# S_Phase_Sense_Signal_Isolation.net
KiCad netlist of a schematic drawn in Altium Designer
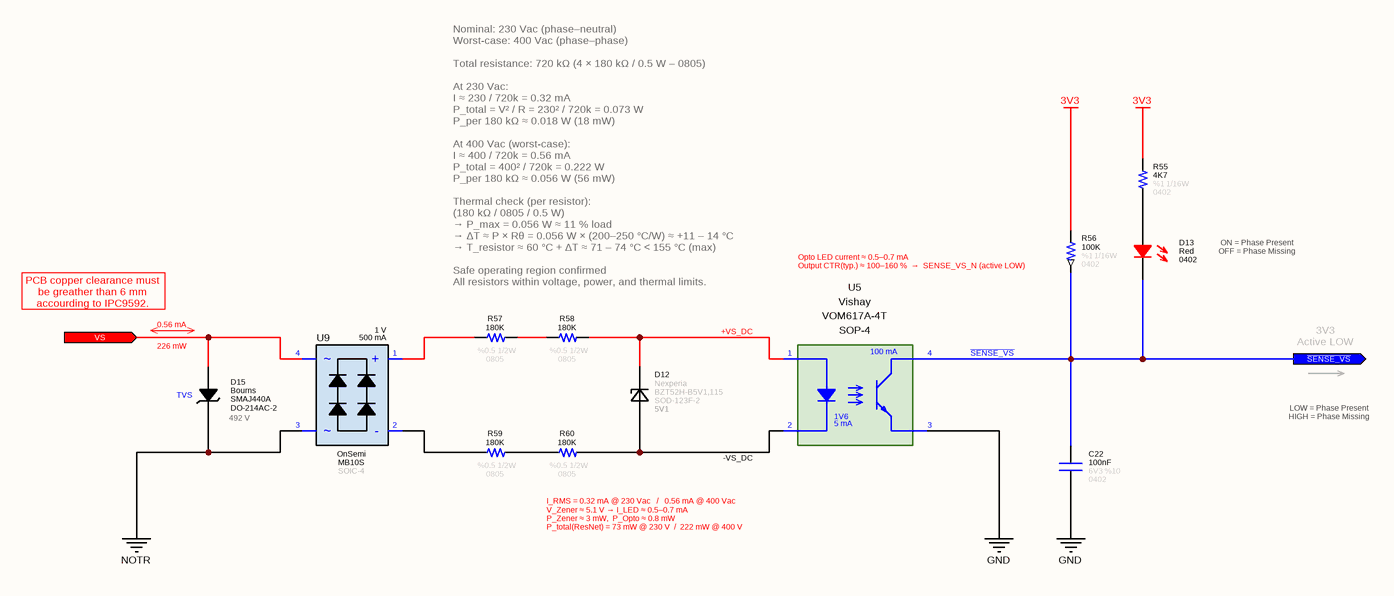
[diagram p0: S Phase Sense Signal Isolation.SchDoc]

(export (version "E")
  (design (tool "Eeschema 10.0.6"))
  (components
    (comp (ref "C22")
      (value "100nF")
      (footprint "CAPACITOR_0402")
      (description "Capacitor (MLCC) - 100nF / 6V3 / 0402")
      (fields
        (field (name "MANUFACTURER PART NUMBER") "04026D104KAT4A")
        (field (name "TOLERANCE") "%10")
        (field (name "VOLTAGE") "6V3")
        (field (name "CASE") "0402")
        (field (name "Comment") "Capacitor - 100nF [0402] (MLCC)")
      )
      (libsource (lib "Akkoyun") (part "Capacitor - 100nF [0402-6V3]"))
    )
    (comp (ref "D12")
      (value "BZT52H-B5V1,115")
      (footprint "SOD-123F-2")
      (description "Zener Diodes BZT52H-B5V1/SOD123F/SOD2")
      (fields
        (field (name "ZENER VOLTAGE") "5V1")
        (field (name "MANUFACTURER NAME") "Nexperia")
        (field (name "MANUFACTURER PART NUMBER") "BZT52H-B5V1,115")
        (field (name "CASE") "SOD-123F-2")
      )
      (libsource (lib "Akkoyun") (part "Diode - BZT52H-B5V1,115"))
    )
    (comp (ref "D13")
      (value "SMD LED (Red)")
      (footprint "LED_0402")
      (description "Standard LEDs - SMD MINI-MOLD ULTRA COMPACT RED")
      (fields
        (field (name "MANUFACTURER PART NUMBER") "SML-P12VTT86R")
        (field (name "CASE") "0402")
        (field (name "COLOR") "Red")
      )
      (libsource (lib "Akkoyun") (part "Diode - LED (0402-Red)"))
    )
    (comp (ref "D15")
      (value "SMAJ440A")
      (footprint "DO-220AA-2")
      (description "ESD Protection Diodes / TVS Diodes 440volts 1uA .6 Amps Uni-Dir")
      (fields
        (field (name "BREAKDOWN VOLTAGE") "492 V")
        (field (name "MANUFACTURER NAME") "Bourns")
        (field (name "MANUFACTURER PART NUMBER") "SMAJ440A")
        (field (name "CASE") "DO-214AC-2")
      )
      (libsource (lib "Akkoyun") (part "Diode - SMAJ440A (TVS)"))
    )
    (comp (ref "R55")
      (value "4K7")
      (footprint "RESISTOR_0402")
      (description "Thick Film Resistors - SMD 1/16 W 4.7 KOhm 1%")
      (fields
        (field (name "MANUFACTURER PART NUMBER") "CRCW04024K70FKED")
        (field (name "TOLERANCE") "%1")
        (field (name "CASE") "0402")
        (field (name "POWER") "1/16W")
        (field (name "Comment") "4K7 - 0402 - %1 - 1/16W")
      )
      (libsource (lib "Akkoyun") (part "Resistor - 4K7 [0402]"))
    )
    (comp (ref "R56")
      (value "100K")
      (footprint "RESISTOR_0402")
      (description "Thick Film Resistors - SMD 1/16 W 100 KOhm 1%")
      (fields
        (field (name "MANUFACTURER PART NUMBER") "CRCW0402100KFKED")
        (field (name "TOLERANCE") "%1")
        (field (name "CASE") "0402")
        (field (name "POWER") "1/16W")
        (field (name "Comment") "100K - 0402 - %1 - 1/16W")
      )
      (libsource (lib "Akkoyun") (part "Resistor - 100K [0402]"))
    )
    (comp (ref "R57")
      (value "180K")
      (footprint "RESISTOR_0805")
      (description "Thick Film Resistors - SMD 0805 180Kohms 0.5W 0.5% AEC-Q200")
      (fields
        (field (name "MANUFACTURER PART NUMBER") "ERJ-P06D1803V")
        (field (name "TOLERANCE") "%0.5")
        (field (name "CASE") "0805")
        (field (name "POWER") "1/2W")
        (field (name "Comment") "180K - 0805 - %0.5 - 1/2W")
      )
      (libsource (lib "Akkoyun") (part "Resistor - 180K [0805]"))
    )
    (comp (ref "R58")
      (value "180K")
      (footprint "RESISTOR_0805")
      (description "Thick Film Resistors - SMD 0805 180Kohms 0.5W 0.5% AEC-Q200")
      (fields
        (field (name "MANUFACTURER PART NUMBER") "ERJ-P06D1803V")
        (field (name "TOLERANCE") "%0.5")
        (field (name "CASE") "0805")
        (field (name "POWER") "1/2W")
        (field (name "Comment") "180K - 0805 - %0.5 - 1/2W")
      )
      (libsource (lib "Akkoyun") (part "Resistor - 180K [0805]"))
    )
    (comp (ref "R59")
      (value "180K")
      (footprint "RESISTOR_0805")
      (description "Thick Film Resistors - SMD 0805 180Kohms 0.5W 0.5% AEC-Q200")
      (fields
        (field (name "MANUFACTURER PART NUMBER") "ERJ-P06D1803V")
        (field (name "TOLERANCE") "%0.5")
        (field (name "CASE") "0805")
        (field (name "POWER") "1/2W")
        (field (name "Comment") "180K - 0805 - %0.5 - 1/2W")
      )
      (libsource (lib "Akkoyun") (part "Resistor - 180K [0805]"))
    )
    (comp (ref "R60")
      (value "180K")
      (footprint "RESISTOR_0805")
      (description "Thick Film Resistors - SMD 0805 180Kohms 0.5W 0.5% AEC-Q200")
      (fields
        (field (name "MANUFACTURER PART NUMBER") "ERJ-P06D1803V")
        (field (name "TOLERANCE") "%0.5")
        (field (name "CASE") "0805")
        (field (name "POWER") "1/2W")
        (field (name "Comment") "180K - 0805 - %0.5 - 1/2W")
      )
      (libsource (lib "Akkoyun") (part "Resistor - 180K [0805]"))
    )
    (comp (ref "U5")
      (value "VOM617A-4T")
      (footprint "SOP-4V2")
      (description "Transistor Output Optocouplers Phototransistor Out CTR 160-320% 5mA")
      (fields
        (field (name "MANUFACTURER PART NUMBER") "VOM617A-4T")
        (field (name "MANUFACTURER NAME") "Vishay")
        (field (name "CASE") "SOP-4")
        (field (name "IF - FORWARD CURRENT") "5 mA")
        (field (name "VF - FORWARD VOLTAGE") "1V6")
        (field (name "MAXIMUM COLLECTOR CURRENT") "100 mA")
      )
      (libsource (lib "Akkoyun") (part "IC - VOM617A"))
    )
    (comp (ref "U9")
      (value "LTV-846S")
      (footprint "SOIC-4")
      (description "Transistor Output Optocouplers Optocplr Phototrans 4-Channel")
      (fields
        (field (name "IF - FORWARD CURRENT") "500 mA")
        (field (name "VF - FORWARD VOLTAGE") "1 V")
        (field (name "MANUFACTURER NAME") "OnSemi")
        (field (name "MANUFACTURER PART NUMBER") "MB10S")
        (field (name "CASE") "SOIC-4")
      )
      (libsource (lib "Akkoyun") (part "IC - MB10S"))
    )
  )
  (nets
    (net (code "1") (name "/+VS_DC") (class "Default")
      (node (ref "D12") (pin "1") (pinfunction "Cathode_1") (pintype "passive"))
      (node (ref "R58") (pin "1") (pinfunction "1_1") (pintype "passive"))
      (node (ref "U5") (pin "1") (pinfunction "LED_Anode_1") (pintype "passive"))
    )
    (net (code "2") (name "/-VS_DC") (class "Default")
      (node (ref "D12") (pin "2") (pinfunction "Anode_2") (pintype "passive"))
      (node (ref "R60") (pin "1") (pinfunction "1_1") (pintype "passive"))
      (node (ref "U5") (pin "2") (pinfunction "LED_Cathode_2") (pintype "passive"))
    )
    (net (code "3") (name "/VS") (class "Default")
      (node (ref "D15") (pin "1") (pinfunction "Anode_1") (pintype "passive"))
      (node (ref "U9") (pin "4") (pinfunction "~_4") (pintype "passive"))
    )
    (net (code "4") (name "/~{SENSE_VS}") (class "Default")
      (node (ref "C22") (pin "2") (pinfunction "2_2") (pintype "passive"))
      (node (ref "D13") (pin "1") (pinfunction "1_1") (pintype "passive"))
      (node (ref "R56") (pin "1") (pinfunction "1_1") (pintype "output"))
      (node (ref "U5") (pin "4") (pinfunction "Collector_4") (pintype "passive"))
    )
    (net (code "5") (name "3V3") (class "Default")
      (node (ref "R55") (pin "2") (pinfunction "2_2") (pintype "passive"))
      (node (ref "R56") (pin "2") (pinfunction "2_2") (pintype "passive"))
    )
    (net (code "6") (name "GND") (class "Default")
      (node (ref "C22") (pin "1") (pinfunction "1_1") (pintype "passive"))
      (node (ref "U5") (pin "3") (pinfunction "Emiter_3") (pintype "passive"))
    )
    (net (code "7") (name "NOTR") (class "Default")
      (node (ref "D15") (pin "2") (pinfunction "Cathode_2") (pintype "passive"))
      (node (ref "U9") (pin "3") (pinfunction "~_3") (pintype "passive"))
    )
    (net (code "8") (name "Net-(D13-Pad2)") (class "Default")
      (node (ref "D13") (pin "2") (pinfunction "2_2") (pintype "passive"))
      (node (ref "R55") (pin "1") (pinfunction "1_1") (pintype "passive"))
    )
    (net (code "9") (name "Net-(R57-Pad1)") (class "Default")
      (node (ref "R57") (pin "1") (pinfunction "1_1") (pintype "passive"))
      (node (ref "R58") (pin "2") (pinfunction "2_2") (pintype "passive"))
    )
    (net (code "10") (name "Net-(R59-Pad1)") (class "Default")
      (node (ref "R59") (pin "1") (pinfunction "1_1") (pintype "passive"))
      (node (ref "R60") (pin "2") (pinfunction "2_2") (pintype "passive"))
    )
    (net (code "11") (name "Net-(U9-+)") (class "Default")
      (node (ref "R57") (pin "2") (pinfunction "2_2") (pintype "passive"))
      (node (ref "U9") (pin "1") (pinfunction "+_1") (pintype "passive"))
    )
    (net (code "12") (name "Net-(U9--)") (class "Default")
      (node (ref "R59") (pin "2") (pinfunction "2_2") (pintype "passive"))
      (node (ref "U9") (pin "2") (pinfunction "-_2") (pintype "passive"))
    )
  )
)
